# Safe_Cracker_Shield.net
KiCad netlist of a schematic drawn in EAGLE
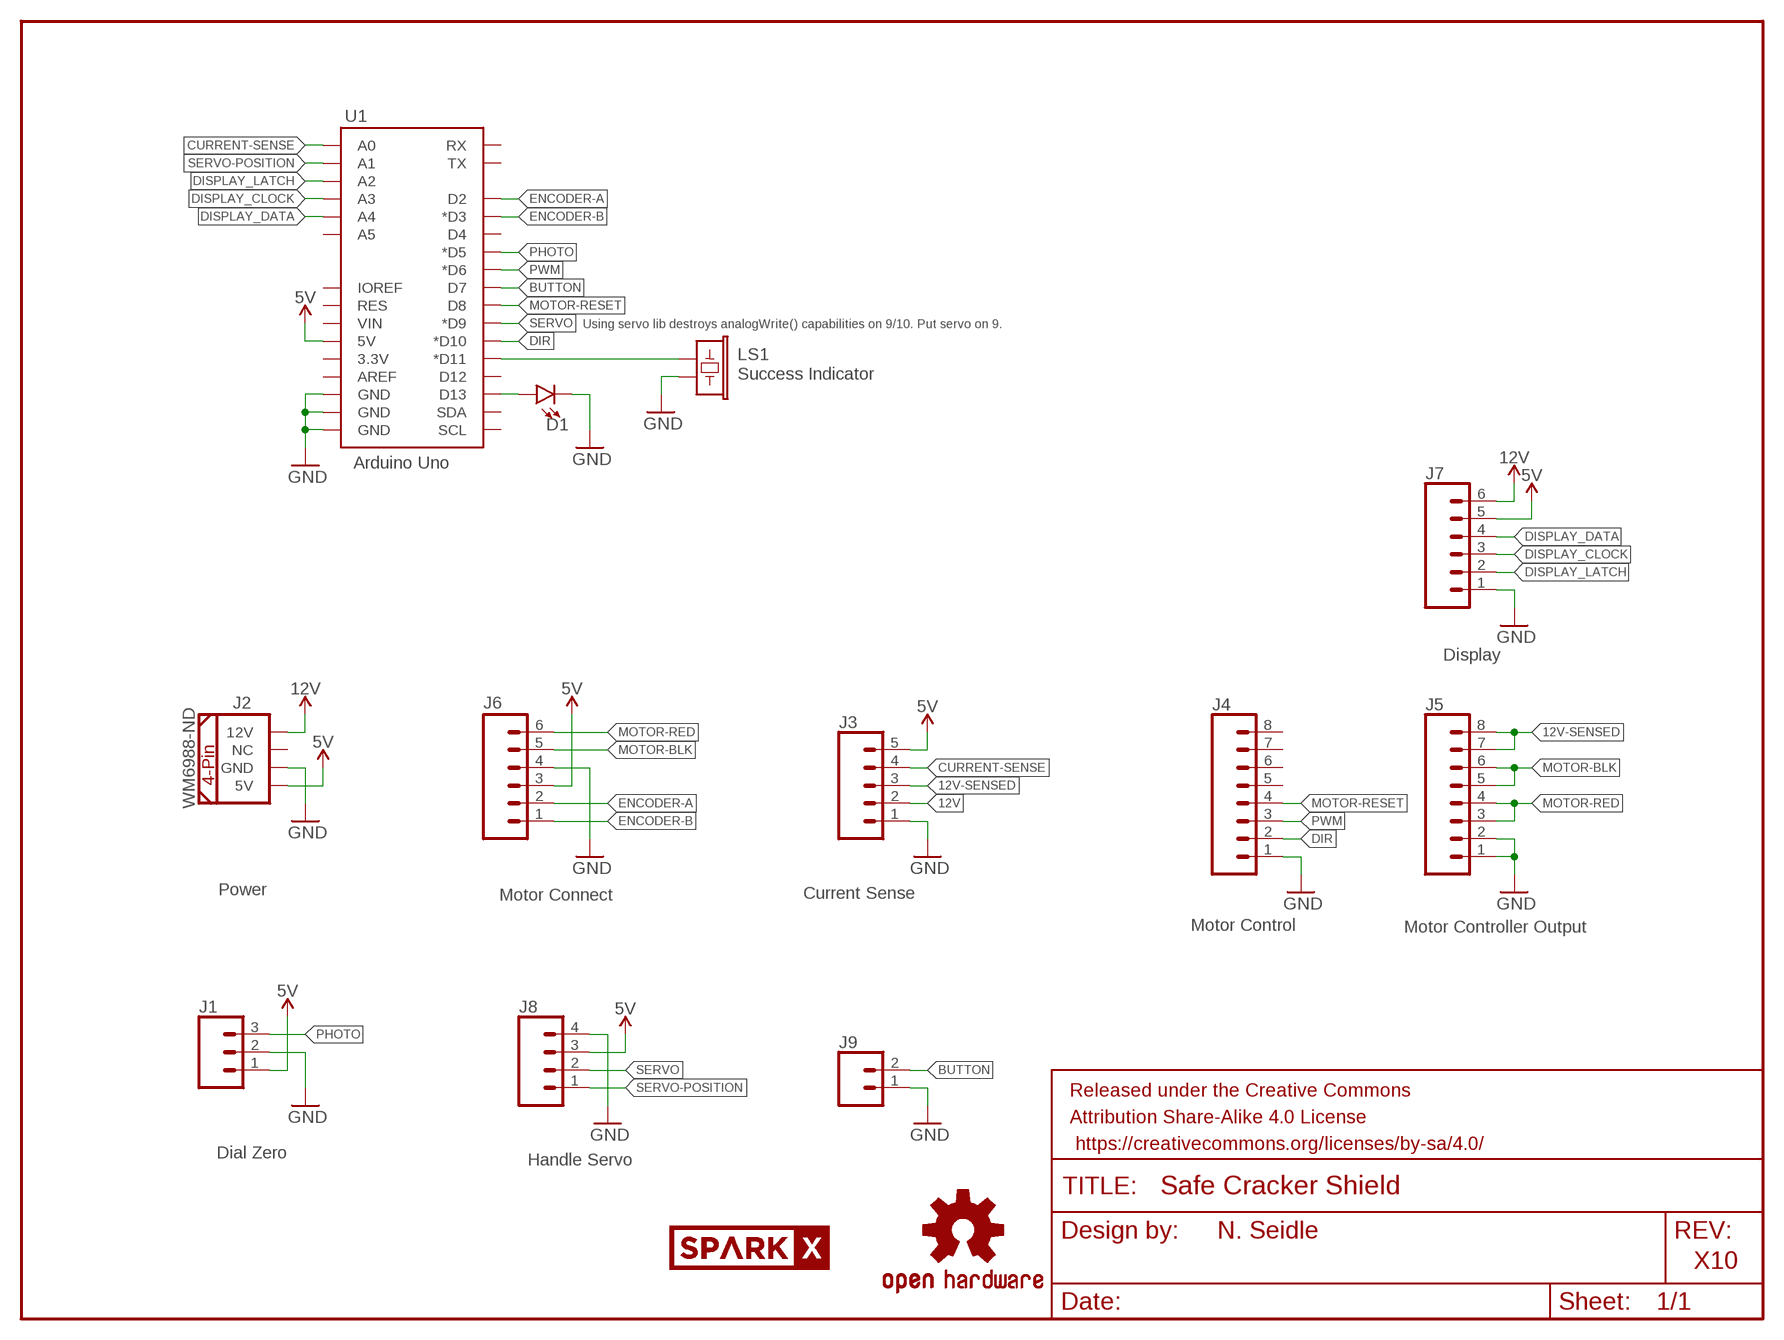
[diagram p0: schematic, sheet 1]

(export (version "E")
  (design (tool "Eeschema 10.0.6"))
  (components
    (comp (ref "D1")
      (value "LED5MM")
      (footprint "eagle-import:LED_5MM")
      (libsource (lib "eagle-import") (part "LED5MM"))
    )
    (comp (ref "FRAME1")
      (value "FRAME-LETTER")
      (footprint "eagle-import:CREATIVE_COMMONS")
      (libsource (lib "eagle-import") (part "FRAME-LETTER"))
    )
    (comp (ref "J1")
      (value "CONN_03JST-PTH-VERT")
      (footprint "eagle-import:JST-3-PTH-VERT")
      (libsource (lib "eagle-import") (part "CONN_03JST-PTH-VERT"))
    )
    (comp (ref "J2")
      (value "Power")
      (footprint "eagle-import:COMPUTER-PERIPHERAL-POWER-RA")
      (libsource (lib "eagle-import") (part "COMPUTER-PERIPHERAL-POWERRA"))
    )
    (comp (ref "J3")
      (value "Current Sense")
      (footprint "eagle-import:1X05")
      (libsource (lib "eagle-import") (part "CONN_05"))
    )
    (comp (ref "J4")
      (value "Motor Control")
      (footprint "eagle-import:1X08")
      (libsource (lib "eagle-import") (part "CONN_08{dblquote}"))
    )
    (comp (ref "J5")
      (value "Motor Controller Output")
      (footprint "eagle-import:1X08")
      (libsource (lib "eagle-import") (part "CONN_08{dblquote}"))
    )
    (comp (ref "J6")
      (value "Motor Connect")
      (footprint "eagle-import:1X06@1")
      (libsource (lib "eagle-import") (part "M06SILK_FEMALE_PTH"))
    )
    (comp (ref "J7")
      (value "CONN_06SILK_FEMALE_PTH")
      (footprint "eagle-import:1X06")
      (libsource (lib "eagle-import") (part "CONN_06SILK_FEMALE_PTH"))
    )
    (comp (ref "J8")
      (value "Handle Servo")
      (footprint "eagle-import:1X04")
      (libsource (lib "eagle-import") (part "CONN_04"))
    )
    (comp (ref "J9")
      (value "CONN_02JST-PTH-VERT")
      (footprint "eagle-import:JST-2-PTH-VERT")
      (libsource (lib "eagle-import") (part "CONN_02JST-PTH-VERT"))
    )
    (comp (ref "LOGO2")
      (value "OSHW-LOGOS")
      (footprint "eagle-import:OSHW-LOGO-S")
      (libsource (lib "eagle-import") (part "OSHW-LOGOS"))
    )
    (comp (ref "LS1")
      (value "Success Indicator")
      (footprint "eagle-import:BUZZER-12MM")
      (libsource (lib "eagle-import") (part "BUZZER-PTH"))
    )
    (comp (ref "U$1")
      (value "SPARKX-LOGO5")
      (footprint "eagle-import:SPARKX-LARGE")
      (libsource (lib "eagle-import") (part "SPARKX-LOGO5"))
    )
    (comp (ref "U1")
      (value "Arduino Uno")
      (footprint "eagle-import:UNO_R3_SHIELD_NOLABELS")
      (libsource (lib "eagle-import") (part "ARDUINO_R3_SHIELDNOLABELS"))
    )
  )
  (nets
    (net (code "1") (name "5V") (class "Default")
      (node (ref "J1") (pin "1") (pinfunction "1_1") (pintype "passive"))
      (node (ref "J2") (pin "5V") (pinfunction "5V_5V") (pintype "passive"))
      (node (ref "J3") (pin "5") (pinfunction "5_5") (pintype "passive"))
      (node (ref "J6") (pin "3") (pinfunction "3_3") (pintype "passive"))
      (node (ref "J7") (pin "5") (pinfunction "5_5") (pintype "passive"))
      (node (ref "J8") (pin "3") (pinfunction "3_3") (pintype "passive"))
      (node (ref "U1") (pin "5V") (pinfunction "5V_5V") (pintype "bidirectional"))
    )
    (net (code "2") (name "12V") (class "Default")
      (node (ref "J2") (pin "12V") (pinfunction "12V_12V") (pintype "passive"))
      (node (ref "J3") (pin "2") (pinfunction "2_2") (pintype "passive"))
      (node (ref "J7") (pin "6") (pinfunction "6_6") (pintype "passive"))
    )
    (net (code "3") (name "12V-SENSED") (class "Default")
      (node (ref "J3") (pin "3") (pinfunction "3_3") (pintype "passive"))
      (node (ref "J5") (pin "7") (pinfunction "7_7") (pintype "passive"))
      (node (ref "J5") (pin "8") (pinfunction "8_8") (pintype "passive"))
    )
    (net (code "4") (name "BUTTON") (class "Default")
      (node (ref "J9") (pin "2") (pinfunction "2_2") (pintype "passive"))
      (node (ref "U1") (pin "D7") (pinfunction "D7_D7") (pintype "bidirectional"))
    )
    (net (code "5") (name "CURRENT-SENSE") (class "Default")
      (node (ref "J3") (pin "4") (pinfunction "4_4") (pintype "passive"))
      (node (ref "U1") (pin "A0") (pinfunction "A0_A0") (pintype "bidirectional"))
    )
    (net (code "6") (name "DIR") (class "Default")
      (node (ref "J4") (pin "2") (pinfunction "2_2") (pintype "passive"))
      (node (ref "U1") (pin "D10") (pinfunction "*D10_D10") (pintype "bidirectional"))
    )
    (net (code "7") (name "DISPLAY_CLOCK") (class "Default")
      (node (ref "J7") (pin "3") (pinfunction "3_3") (pintype "passive"))
      (node (ref "U1") (pin "A3") (pinfunction "A3_A3") (pintype "bidirectional"))
    )
    (net (code "8") (name "DISPLAY_DATA") (class "Default")
      (node (ref "J7") (pin "4") (pinfunction "4_4") (pintype "passive"))
      (node (ref "U1") (pin "A4") (pinfunction "A4_A4") (pintype "bidirectional"))
    )
    (net (code "9") (name "DISPLAY_LATCH") (class "Default")
      (node (ref "J7") (pin "2") (pinfunction "2_2") (pintype "passive"))
      (node (ref "U1") (pin "A2") (pinfunction "A2_A2") (pintype "bidirectional"))
    )
    (net (code "10") (name "ENCODER-A") (class "Default")
      (node (ref "J6") (pin "2") (pinfunction "2_2") (pintype "passive"))
      (node (ref "U1") (pin "D2") (pinfunction "D2_D2") (pintype "bidirectional"))
    )
    (net (code "11") (name "ENCODER-B") (class "Default")
      (node (ref "J6") (pin "1") (pinfunction "1_1") (pintype "passive"))
      (node (ref "U1") (pin "D3") (pinfunction "*D3_D3") (pintype "bidirectional"))
    )
    (net (code "12") (name "GND") (class "Default")
      (node (ref "D1") (pin "K") (pinfunction "C_K") (pintype "passive"))
      (node (ref "J1") (pin "2") (pinfunction "2_2") (pintype "passive"))
      (node (ref "J2") (pin "GND") (pinfunction "GND_GND") (pintype "passive"))
      (node (ref "J3") (pin "1") (pinfunction "1_1") (pintype "passive"))
      (node (ref "J4") (pin "1") (pinfunction "1_1") (pintype "passive"))
      (node (ref "J5") (pin "1") (pinfunction "1_1") (pintype "passive"))
      (node (ref "J5") (pin "2") (pinfunction "2_2") (pintype "passive"))
      (node (ref "J6") (pin "4") (pinfunction "4_4") (pintype "passive"))
      (node (ref "J7") (pin "1") (pinfunction "1_1") (pintype "passive"))
      (node (ref "J8") (pin "4") (pinfunction "4_4") (pintype "passive"))
      (node (ref "J9") (pin "1") (pinfunction "1_1") (pintype "passive"))
      (node (ref "LS1") (pin "-") (pinfunction "2_-") (pintype "passive"))
      (node (ref "U1") (pin "GND@0") (pinfunction "GND_GND@0") (pintype "bidirectional"))
      (node (ref "U1") (pin "GND@1") (pinfunction "GND_GND@1") (pintype "bidirectional"))
      (node (ref "U1") (pin "GND@2") (pinfunction "GND_GND@2") (pintype "bidirectional"))
    )
    (net (code "13") (name "MOTOR-BLK") (class "Default")
      (node (ref "J5") (pin "5") (pinfunction "5_5") (pintype "passive"))
      (node (ref "J5") (pin "6") (pinfunction "6_6") (pintype "passive"))
      (node (ref "J6") (pin "5") (pinfunction "5_5") (pintype "passive"))
    )
    (net (code "14") (name "MOTOR-RED") (class "Default")
      (node (ref "J5") (pin "3") (pinfunction "3_3") (pintype "passive"))
      (node (ref "J5") (pin "4") (pinfunction "4_4") (pintype "passive"))
      (node (ref "J6") (pin "6") (pinfunction "6_6") (pintype "passive"))
    )
    (net (code "15") (name "MOTOR-RESET") (class "Default")
      (node (ref "J4") (pin "4") (pinfunction "4_4") (pintype "passive"))
      (node (ref "U1") (pin "D8") (pinfunction "D8_D8") (pintype "bidirectional"))
    )
    (net (code "16") (name "Net-(D1-PadA)") (class "Default")
      (node (ref "D1") (pin "A") (pinfunction "A_A") (pintype "passive"))
      (node (ref "U1") (pin "D13") (pinfunction "D13_D13") (pintype "bidirectional"))
    )
    (net (code "17") (name "Net-(LS1-1)") (class "Default")
      (node (ref "LS1") (pin "+") (pinfunction "1_+") (pintype "passive"))
      (node (ref "U1") (pin "D11") (pinfunction "*D11_D11") (pintype "bidirectional"))
    )
    (net (code "18") (name "PHOTO") (class "Default")
      (node (ref "J1") (pin "3") (pinfunction "3_3") (pintype "passive"))
      (node (ref "U1") (pin "D5") (pinfunction "*D5_D5") (pintype "bidirectional"))
    )
    (net (code "19") (name "PWM") (class "Default")
      (node (ref "J4") (pin "3") (pinfunction "3_3") (pintype "passive"))
      (node (ref "U1") (pin "D6") (pinfunction "*D6_D6") (pintype "bidirectional"))
    )
    (net (code "20") (name "SERVO") (class "Default")
      (node (ref "J8") (pin "2") (pinfunction "2_2") (pintype "passive"))
      (node (ref "U1") (pin "D9") (pinfunction "*D9_D9") (pintype "bidirectional"))
    )
    (net (code "21") (name "SERVO-POSITION") (class "Default")
      (node (ref "J8") (pin "1") (pinfunction "1_1") (pintype "passive"))
      (node (ref "U1") (pin "A1") (pinfunction "A1_A1") (pintype "bidirectional"))
    )
    (net (code "22") (name "unconnected-(J2-PadNC)") (class "Default")
      (node (ref "J2") (pin "NC") (pinfunction "NC_NC") (pintype "passive"))
    )
    (net (code "23") (name "unconnected-(J4-Pad5)") (class "Default")
      (node (ref "J4") (pin "5") (pinfunction "5_5") (pintype "passive"))
    )
    (net (code "24") (name "unconnected-(J4-Pad6)") (class "Default")
      (node (ref "J4") (pin "6") (pinfunction "6_6") (pintype "passive"))
    )
    (net (code "25") (name "unconnected-(J4-Pad7)") (class "Default")
      (node (ref "J4") (pin "7") (pinfunction "7_7") (pintype "passive"))
    )
    (net (code "26") (name "unconnected-(J4-Pad8)") (class "Default")
      (node (ref "J4") (pin "8") (pinfunction "8_8") (pintype "passive"))
    )
    (net (code "27") (name "unconnected-(U1-Pad3.3V)") (class "Default")
      (node (ref "U1") (pin "3.3V") (pinfunction "3.3V_3.3V") (pintype "bidirectional"))
    )
    (net (code "28") (name "unconnected-(U1-PadA5)") (class "Default")
      (node (ref "U1") (pin "A5") (pinfunction "A5_A5") (pintype "bidirectional"))
    )
    (net (code "29") (name "unconnected-(U1-PadAREF)") (class "Default")
      (node (ref "U1") (pin "AREF") (pinfunction "AREF_AREF") (pintype "bidirectional"))
    )
    (net (code "30") (name "unconnected-(U1-PadD4)") (class "Default")
      (node (ref "U1") (pin "D4") (pinfunction "D4_D4") (pintype "bidirectional"))
    )
    (net (code "31") (name "unconnected-(U1-PadD12)") (class "Default")
      (node (ref "U1") (pin "D12") (pinfunction "D12_D12") (pintype "bidirectional"))
    )
    (net (code "32") (name "unconnected-(U1-PadIOREF)") (class "Default")
      (node (ref "U1") (pin "IOREF") (pinfunction "IOREF_IOREF") (pintype "bidirectional"))
    )
    (net (code "33") (name "unconnected-(U1-PadRES)") (class "Default")
      (node (ref "U1") (pin "RES") (pinfunction "RES_RES") (pintype "bidirectional"))
    )
    (net (code "34") (name "unconnected-(U1-PadRX)") (class "Default")
      (node (ref "U1") (pin "RX") (pinfunction "RX_RX") (pintype "bidirectional"))
    )
    (net (code "35") (name "unconnected-(U1-PadSCL)") (class "Default")
      (node (ref "U1") (pin "SCL") (pinfunction "SCL_SCL") (pintype "bidirectional"))
    )
    (net (code "36") (name "unconnected-(U1-PadSDA)") (class "Default")
      (node (ref "U1") (pin "SDA") (pinfunction "SDA_SDA") (pintype "bidirectional"))
    )
    (net (code "37") (name "unconnected-(U1-PadTX)") (class "Default")
      (node (ref "U1") (pin "TX") (pinfunction "TX_TX") (pintype "bidirectional"))
    )
    (net (code "38") (name "unconnected-(U1-PadVIN)") (class "Default")
      (node (ref "U1") (pin "VIN") (pinfunction "VIN_VIN") (pintype "bidirectional"))
    )
  )
)
